# 360_led_stick_5_layer.net
KiCad netlist of a schematic drawn in EAGLE
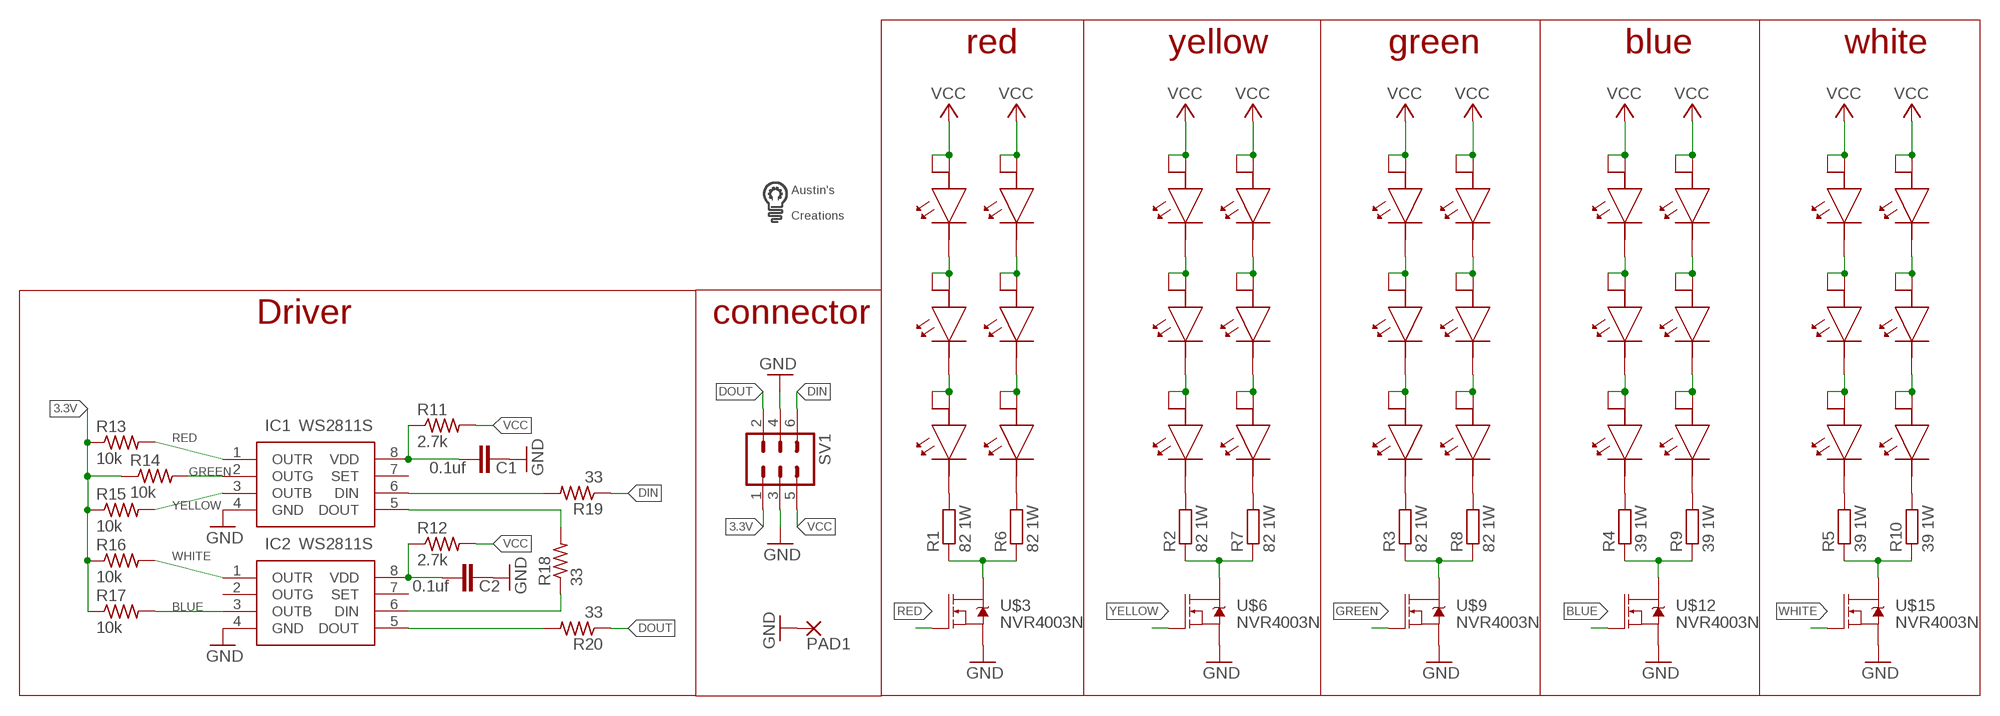
[diagram p0: schematic, sheet 1]

(export (version "E")
  (design (tool "Eeschema 10.0.6"))
  (components
    (comp (ref "C1")
      (value "0.1uf")
      (footprint "eagle-import:C0603K")
      (libsource (lib "eagle-import") (part "C-EUC0603K"))
    )
    (comp (ref "C2")
      (value "0.1uf")
      (footprint "eagle-import:C0603K")
      (libsource (lib "eagle-import") (part "C-EUC0603K"))
    )
    (comp (ref "IC1")
      (value "WS2811S")
      (footprint "eagle-import:SOIC127P600X175-8N")
      (fields (field (name "MANUFACTURER_PART_NUMBER") "ws2811s"))
      (libsource (lib "eagle-import") (part "WS2811S"))
    )
    (comp (ref "IC2")
      (value "WS2811S")
      (footprint "eagle-import:SOIC127P600X175-8N")
      (fields (field (name "MANUFACTURER_PART_NUMBER") "ws2811s"))
      (libsource (lib "eagle-import") (part "WS2811S"))
    )
    (comp (ref "PAD1")
      (value "WIREPADSMD1,27-254")
      (footprint "eagle-import:SMD1,27-2,54")
      (libsource (lib "eagle-import") (part "WIREPADSMD1,27-254"))
    )
    (comp (ref "R1")
      (value "82 1W")
      (footprint "eagle-import:R1210")
      (libsource (lib "eagle-import") (part "R-EU_R1210"))
    )
    (comp (ref "R2")
      (value "82 1W")
      (footprint "eagle-import:R1210")
      (libsource (lib "eagle-import") (part "R-EU_R1210"))
    )
    (comp (ref "R3")
      (value "82 1W")
      (footprint "eagle-import:R1210")
      (libsource (lib "eagle-import") (part "R-EU_R1210"))
    )
    (comp (ref "R4")
      (value "39 1W")
      (footprint "eagle-import:R1210")
      (libsource (lib "eagle-import") (part "R-EU_R1210"))
    )
    (comp (ref "R5")
      (value "39 1W")
      (footprint "eagle-import:R1210")
      (libsource (lib "eagle-import") (part "R-EU_R1210"))
    )
    (comp (ref "R6")
      (value "82 1W")
      (footprint "eagle-import:R1210")
      (libsource (lib "eagle-import") (part "R-EU_R1210"))
    )
    (comp (ref "R7")
      (value "82 1W")
      (footprint "eagle-import:R1210")
      (libsource (lib "eagle-import") (part "R-EU_R1210"))
    )
    (comp (ref "R8")
      (value "82 1W")
      (footprint "eagle-import:R1210")
      (libsource (lib "eagle-import") (part "R-EU_R1210"))
    )
    (comp (ref "R9")
      (value "39 1W")
      (footprint "eagle-import:R1210")
      (libsource (lib "eagle-import") (part "R-EU_R1210"))
    )
    (comp (ref "R10")
      (value "39 1W")
      (footprint "eagle-import:R1210")
      (libsource (lib "eagle-import") (part "R-EU_R1210"))
    )
    (comp (ref "R11")
      (value "2.7k")
      (footprint "eagle-import:R0603")
      (libsource (lib "eagle-import") (part "R-US_R0603"))
    )
    (comp (ref "R12")
      (value "2.7k")
      (footprint "eagle-import:R0603")
      (libsource (lib "eagle-import") (part "R-US_R0603"))
    )
    (comp (ref "R13")
      (value "10k")
      (footprint "eagle-import:R0603")
      (libsource (lib "eagle-import") (part "R-US_R0603"))
    )
    (comp (ref "R14")
      (value "10k")
      (footprint "eagle-import:R0603")
      (libsource (lib "eagle-import") (part "R-US_R0603"))
    )
    (comp (ref "R15")
      (value "10k")
      (footprint "eagle-import:R0603")
      (libsource (lib "eagle-import") (part "R-US_R0603"))
    )
    (comp (ref "R16")
      (value "10k")
      (footprint "eagle-import:R0603")
      (libsource (lib "eagle-import") (part "R-US_R0603"))
    )
    (comp (ref "R17")
      (value "10k")
      (footprint "eagle-import:R0603")
      (libsource (lib "eagle-import") (part "R-US_R0603"))
    )
    (comp (ref "R18")
      (value "33")
      (footprint "eagle-import:R0603")
      (libsource (lib "eagle-import") (part "R-US_R0603"))
    )
    (comp (ref "R19")
      (value "33")
      (footprint "eagle-import:R0603")
      (libsource (lib "eagle-import") (part "R-US_R0603"))
    )
    (comp (ref "R20")
      (value "33")
      (footprint "eagle-import:R0603")
      (libsource (lib "eagle-import") (part "R-US_R0603"))
    )
    (comp (ref "SV1")
      (value "MA03-2")
      (footprint "eagle-import:MA03-2")
      (libsource (lib "eagle-import") (part "MA03-2"))
    )
    (comp (ref "U$1")
      (value "5730LED")
      (footprint "eagle-import:5730LED")
      (libsource (lib "eagle-import") (part "5730LED"))
    )
    (comp (ref "U$2")
      (value "5730LED")
      (footprint "eagle-import:5730LED")
      (libsource (lib "eagle-import") (part "5730LED"))
    )
    (comp (ref "U$3")
      (value "NVR4003N")
      (footprint "eagle-import:SOT23")
      (libsource (lib "eagle-import") (part "NVR4003N"))
    )
    (comp (ref "U$4")
      (value "5730LED")
      (footprint "eagle-import:5730LED")
      (libsource (lib "eagle-import") (part "5730LED"))
    )
    (comp (ref "U$5")
      (value "5730LED")
      (footprint "eagle-import:5730LED")
      (libsource (lib "eagle-import") (part "5730LED"))
    )
    (comp (ref "U$6")
      (value "NVR4003N")
      (footprint "eagle-import:SOT23")
      (libsource (lib "eagle-import") (part "NVR4003N"))
    )
    (comp (ref "U$7")
      (value "5730LED")
      (footprint "eagle-import:5730LED")
      (libsource (lib "eagle-import") (part "5730LED"))
    )
    (comp (ref "U$8")
      (value "5730LED")
      (footprint "eagle-import:5730LED")
      (libsource (lib "eagle-import") (part "5730LED"))
    )
    (comp (ref "U$9")
      (value "NVR4003N")
      (footprint "eagle-import:SOT23")
      (libsource (lib "eagle-import") (part "NVR4003N"))
    )
    (comp (ref "U$10")
      (value "5730LED")
      (footprint "eagle-import:5730LED")
      (libsource (lib "eagle-import") (part "5730LED"))
    )
    (comp (ref "U$11")
      (value "5730LED")
      (footprint "eagle-import:5730LED")
      (libsource (lib "eagle-import") (part "5730LED"))
    )
    (comp (ref "U$12")
      (value "NVR4003N")
      (footprint "eagle-import:SOT23")
      (libsource (lib "eagle-import") (part "NVR4003N"))
    )
    (comp (ref "U$13")
      (value "5730LED")
      (footprint "eagle-import:5730LED")
      (libsource (lib "eagle-import") (part "5730LED"))
    )
    (comp (ref "U$14")
      (value "5730LED")
      (footprint "eagle-import:5730LED")
      (libsource (lib "eagle-import") (part "5730LED"))
    )
    (comp (ref "U$15")
      (value "NVR4003N")
      (footprint "eagle-import:SOT23")
      (libsource (lib "eagle-import") (part "NVR4003N"))
    )
    (comp (ref "U$16")
      (value "5730LED")
      (footprint "eagle-import:5730LED")
      (libsource (lib "eagle-import") (part "5730LED"))
    )
    (comp (ref "U$17")
      (value "5730LED")
      (footprint "eagle-import:5730LED")
      (libsource (lib "eagle-import") (part "5730LED"))
    )
    (comp (ref "U$18")
      (value "5730LED")
      (footprint "eagle-import:5730LED")
      (libsource (lib "eagle-import") (part "5730LED"))
    )
    (comp (ref "U$19")
      (value "5730LED")
      (footprint "eagle-import:5730LED")
      (libsource (lib "eagle-import") (part "5730LED"))
    )
    (comp (ref "U$20")
      (value "5730LED")
      (footprint "eagle-import:5730LED")
      (libsource (lib "eagle-import") (part "5730LED"))
    )
    (comp (ref "U$21")
      (value "LOGO")
      (footprint "eagle-import:LOGO")
      (libsource (lib "eagle-import") (part "LOGO"))
    )
    (comp (ref "U$22")
      (value "5730LED")
      (footprint "eagle-import:5730LED")
      (libsource (lib "eagle-import") (part "5730LED"))
    )
    (comp (ref "U$23")
      (value "5730LED")
      (footprint "eagle-import:5730LED")
      (libsource (lib "eagle-import") (part "5730LED"))
    )
    (comp (ref "U$24")
      (value "5730LED")
      (footprint "eagle-import:5730LED")
      (libsource (lib "eagle-import") (part "5730LED"))
    )
    (comp (ref "U$25")
      (value "5730LED")
      (footprint "eagle-import:5730LED")
      (libsource (lib "eagle-import") (part "5730LED"))
    )
    (comp (ref "U$26")
      (value "5730LED")
      (footprint "eagle-import:5730LED")
      (libsource (lib "eagle-import") (part "5730LED"))
    )
    (comp (ref "U$27")
      (value "5730LED")
      (footprint "eagle-import:5730LED")
      (libsource (lib "eagle-import") (part "5730LED"))
    )
    (comp (ref "U$28")
      (value "5730LED")
      (footprint "eagle-import:5730LED")
      (libsource (lib "eagle-import") (part "5730LED"))
    )
    (comp (ref "U$29")
      (value "5730LED")
      (footprint "eagle-import:5730LED")
      (libsource (lib "eagle-import") (part "5730LED"))
    )
    (comp (ref "U$30")
      (value "5730LED")
      (footprint "eagle-import:5730LED")
      (libsource (lib "eagle-import") (part "5730LED"))
    )
    (comp (ref "U$31")
      (value "5730LED")
      (footprint "eagle-import:5730LED")
      (libsource (lib "eagle-import") (part "5730LED"))
    )
    (comp (ref "U$32")
      (value "5730LED")
      (footprint "eagle-import:5730LED")
      (libsource (lib "eagle-import") (part "5730LED"))
    )
    (comp (ref "U$33")
      (value "5730LED")
      (footprint "eagle-import:5730LED")
      (libsource (lib "eagle-import") (part "5730LED"))
    )
    (comp (ref "U$34")
      (value "5730LED")
      (footprint "eagle-import:5730LED")
      (libsource (lib "eagle-import") (part "5730LED"))
    )
    (comp (ref "U$35")
      (value "5730LED")
      (footprint "eagle-import:5730LED")
      (libsource (lib "eagle-import") (part "5730LED"))
    )
    (comp (ref "U$36")
      (value "5730LED")
      (footprint "eagle-import:5730LED")
      (libsource (lib "eagle-import") (part "5730LED"))
    )
  )
  (nets
    (net (code "1") (name "3.3V") (class "Default")
      (node (ref "R13") (pin "1") (pinfunction "1_1") (pintype "passive"))
      (node (ref "R14") (pin "1") (pinfunction "1_1") (pintype "passive"))
      (node (ref "R15") (pin "1") (pinfunction "1_1") (pintype "passive"))
      (node (ref "R16") (pin "1") (pinfunction "1_1") (pintype "passive"))
      (node (ref "R17") (pin "1") (pinfunction "1_1") (pintype "passive"))
      (node (ref "SV1") (pin "1") (pinfunction "1_1") (pintype "passive"))
    )
    (net (code "2") (name "BLUE") (class "Default")
      (node (ref "IC2") (pin "3") (pinfunction "OUTB_3") (pintype "output"))
      (node (ref "R17") (pin "2") (pinfunction "2_2") (pintype "passive"))
      (node (ref "U$12") (pin "2") (pinfunction "G_2") (pintype "bidirectional"))
    )
    (net (code "3") (name "DIN") (class "Default")
      (node (ref "R19") (pin "1") (pinfunction "1_1") (pintype "passive"))
      (node (ref "SV1") (pin "6") (pinfunction "6_6") (pintype "passive"))
    )
    (net (code "4") (name "DOUT") (class "Default")
      (node (ref "R20") (pin "1") (pinfunction "1_1") (pintype "passive"))
      (node (ref "SV1") (pin "2") (pinfunction "2_2") (pintype "passive"))
    )
    (net (code "5") (name "GND") (class "Default")
      (node (ref "C1") (pin "1") (pinfunction "1_1") (pintype "passive"))
      (node (ref "C2") (pin "1") (pinfunction "1_1") (pintype "passive"))
      (node (ref "IC1") (pin "4") (pinfunction "GND_4") (pintype "power_in"))
      (node (ref "IC2") (pin "4") (pinfunction "GND_4") (pintype "power_in"))
      (node (ref "PAD1") (pin "1") (pinfunction "P_1") (pintype "passive"))
      (node (ref "SV1") (pin "3") (pinfunction "3_3") (pintype "passive"))
      (node (ref "SV1") (pin "4") (pinfunction "4_4") (pintype "passive"))
      (node (ref "U$12") (pin "3") (pinfunction "S_3") (pintype "bidirectional"))
      (node (ref "U$15") (pin "3") (pinfunction "S_3") (pintype "bidirectional"))
      (node (ref "U$3") (pin "3") (pinfunction "S_3") (pintype "bidirectional"))
      (node (ref "U$6") (pin "3") (pinfunction "S_3") (pintype "bidirectional"))
      (node (ref "U$9") (pin "3") (pinfunction "S_3") (pintype "bidirectional"))
    )
    (net (code "6") (name "GREEN") (class "Default")
      (node (ref "IC1") (pin "2") (pinfunction "OUTG_2") (pintype "output"))
      (node (ref "R14") (pin "2") (pinfunction "2_2") (pintype "passive"))
      (node (ref "U$9") (pin "2") (pinfunction "G_2") (pintype "bidirectional"))
    )
    (net (code "7") (name "Net-(IC1-DIN)") (class "Default")
      (node (ref "IC1") (pin "6") (pinfunction "DIN_6") (pintype "input"))
      (node (ref "R19") (pin "2") (pinfunction "2_2") (pintype "passive"))
    )
    (net (code "8") (name "Net-(IC1-DOUT)") (class "Default")
      (node (ref "IC1") (pin "5") (pinfunction "DOUT_5") (pintype "bidirectional"))
      (node (ref "R18") (pin "2") (pinfunction "2_2") (pintype "passive"))
    )
    (net (code "9") (name "Net-(IC1-VDD)") (class "Default")
      (node (ref "C1") (pin "2") (pinfunction "2_2") (pintype "passive"))
      (node (ref "IC1") (pin "8") (pinfunction "VDD_8") (pintype "power_in"))
      (node (ref "R11") (pin "1") (pinfunction "1_1") (pintype "passive"))
    )
    (net (code "10") (name "Net-(IC2-DIN)") (class "Default")
      (node (ref "IC2") (pin "6") (pinfunction "DIN_6") (pintype "input"))
      (node (ref "R18") (pin "1") (pinfunction "1_1") (pintype "passive"))
    )
    (net (code "11") (name "Net-(IC2-DOUT)") (class "Default")
      (node (ref "IC2") (pin "5") (pinfunction "DOUT_5") (pintype "bidirectional"))
      (node (ref "R20") (pin "2") (pinfunction "2_2") (pintype "passive"))
    )
    (net (code "12") (name "Net-(IC2-VDD)") (class "Default")
      (node (ref "C2") (pin "2") (pinfunction "2_2") (pintype "passive"))
      (node (ref "IC2") (pin "8") (pinfunction "VDD_8") (pintype "power_in"))
      (node (ref "R12") (pin "1") (pinfunction "1_1") (pintype "passive"))
    )
    (net (code "13") (name "Net-(R1-Pad2)") (class "Default")
      (node (ref "R1") (pin "2") (pinfunction "2_2") (pintype "passive"))
      (node (ref "U$4") (pin "P$2") (pinfunction "P$2_P$2") (pintype "bidirectional"))
    )
    (net (code "14") (name "Net-(R2-Pad2)") (class "Default")
      (node (ref "R2") (pin "2") (pinfunction "2_2") (pintype "passive"))
      (node (ref "U$8") (pin "P$2") (pinfunction "P$2_P$2") (pintype "bidirectional"))
    )
    (net (code "15") (name "Net-(R3-Pad2)") (class "Default")
      (node (ref "R3") (pin "2") (pinfunction "2_2") (pintype "passive"))
      (node (ref "U$13") (pin "P$2") (pinfunction "P$2_P$2") (pintype "bidirectional"))
    )
    (net (code "16") (name "Net-(R4-Pad2)") (class "Default")
      (node (ref "R4") (pin "2") (pinfunction "2_2") (pintype "passive"))
      (node (ref "U$17") (pin "P$2") (pinfunction "P$2_P$2") (pintype "bidirectional"))
    )
    (net (code "17") (name "Net-(R5-Pad2)") (class "Default")
      (node (ref "R5") (pin "2") (pinfunction "2_2") (pintype "passive"))
      (node (ref "U$20") (pin "P$2") (pinfunction "P$2_P$2") (pintype "bidirectional"))
    )
    (net (code "18") (name "Net-(R6-Pad2)") (class "Default")
      (node (ref "R6") (pin "2") (pinfunction "2_2") (pintype "passive"))
      (node (ref "U$24") (pin "P$2") (pinfunction "P$2_P$2") (pintype "bidirectional"))
    )
    (net (code "19") (name "Net-(R7-Pad2)") (class "Default")
      (node (ref "R7") (pin "2") (pinfunction "2_2") (pintype "passive"))
      (node (ref "U$27") (pin "P$2") (pinfunction "P$2_P$2") (pintype "bidirectional"))
    )
    (net (code "20") (name "Net-(R8-Pad2)") (class "Default")
      (node (ref "R8") (pin "2") (pinfunction "2_2") (pintype "passive"))
      (node (ref "U$30") (pin "P$2") (pinfunction "P$2_P$2") (pintype "bidirectional"))
    )
    (net (code "21") (name "Net-(R9-Pad2)") (class "Default")
      (node (ref "R9") (pin "2") (pinfunction "2_2") (pintype "passive"))
      (node (ref "U$33") (pin "P$2") (pinfunction "P$2_P$2") (pintype "bidirectional"))
    )
    (net (code "22") (name "Net-(R10-Pad2)") (class "Default")
      (node (ref "R10") (pin "2") (pinfunction "2_2") (pintype "passive"))
      (node (ref "U$36") (pin "P$2") (pinfunction "P$2_P$2") (pintype "bidirectional"))
    )
    (net (code "23") (name "Net-(U$1-PadP$2)") (class "Default")
      (node (ref "U$1") (pin "P$2") (pinfunction "P$2_P$2") (pintype "bidirectional"))
      (node (ref "U$2") (pin "P$1") (pinfunction "P$1_P$1") (pintype "bidirectional"))
      (node (ref "U$2") (pin "P$3") (pinfunction "P$3_P$3") (pintype "bidirectional"))
    )
    (net (code "24") (name "Net-(U$2-PadP$2)") (class "Default")
      (node (ref "U$2") (pin "P$2") (pinfunction "P$2_P$2") (pintype "bidirectional"))
      (node (ref "U$4") (pin "P$1") (pinfunction "P$1_P$1") (pintype "bidirectional"))
      (node (ref "U$4") (pin "P$3") (pinfunction "P$3_P$3") (pintype "bidirectional"))
    )
    (net (code "25") (name "Net-(U$3-D)") (class "Default")
      (node (ref "R1") (pin "1") (pinfunction "1_1") (pintype "passive"))
      (node (ref "R6") (pin "1") (pinfunction "1_1") (pintype "passive"))
      (node (ref "U$3") (pin "1") (pinfunction "D_1") (pintype "bidirectional"))
    )
    (net (code "26") (name "Net-(U$5-PadP$2)") (class "Default")
      (node (ref "U$5") (pin "P$2") (pinfunction "P$2_P$2") (pintype "bidirectional"))
      (node (ref "U$7") (pin "P$1") (pinfunction "P$1_P$1") (pintype "bidirectional"))
      (node (ref "U$7") (pin "P$3") (pinfunction "P$3_P$3") (pintype "bidirectional"))
    )
    (net (code "27") (name "Net-(U$6-D)") (class "Default")
      (node (ref "R2") (pin "1") (pinfunction "1_1") (pintype "passive"))
      (node (ref "R7") (pin "1") (pinfunction "1_1") (pintype "passive"))
      (node (ref "U$6") (pin "1") (pinfunction "D_1") (pintype "bidirectional"))
    )
    (net (code "28") (name "Net-(U$7-PadP$2)") (class "Default")
      (node (ref "U$7") (pin "P$2") (pinfunction "P$2_P$2") (pintype "bidirectional"))
      (node (ref "U$8") (pin "P$1") (pinfunction "P$1_P$1") (pintype "bidirectional"))
      (node (ref "U$8") (pin "P$3") (pinfunction "P$3_P$3") (pintype "bidirectional"))
    )
    (net (code "29") (name "Net-(U$9-D)") (class "Default")
      (node (ref "R3") (pin "1") (pinfunction "1_1") (pintype "passive"))
      (node (ref "R8") (pin "1") (pinfunction "1_1") (pintype "passive"))
      (node (ref "U$9") (pin "1") (pinfunction "D_1") (pintype "bidirectional"))
    )
    (net (code "30") (name "Net-(U$10-PadP$2)") (class "Default")
      (node (ref "U$10") (pin "P$2") (pinfunction "P$2_P$2") (pintype "bidirectional"))
      (node (ref "U$11") (pin "P$1") (pinfunction "P$1_P$1") (pintype "bidirectional"))
      (node (ref "U$11") (pin "P$3") (pinfunction "P$3_P$3") (pintype "bidirectional"))
    )
    (net (code "31") (name "Net-(U$11-PadP$2)") (class "Default")
      (node (ref "U$11") (pin "P$2") (pinfunction "P$2_P$2") (pintype "bidirectional"))
      (node (ref "U$13") (pin "P$1") (pinfunction "P$1_P$1") (pintype "bidirectional"))
      (node (ref "U$13") (pin "P$3") (pinfunction "P$3_P$3") (pintype "bidirectional"))
    )
    (net (code "32") (name "Net-(U$12-D)") (class "Default")
      (node (ref "R4") (pin "1") (pinfunction "1_1") (pintype "passive"))
      (node (ref "R9") (pin "1") (pinfunction "1_1") (pintype "passive"))
      (node (ref "U$12") (pin "1") (pinfunction "D_1") (pintype "bidirectional"))
    )
    (net (code "33") (name "Net-(U$14-PadP$2)") (class "Default")
      (node (ref "U$14") (pin "P$2") (pinfunction "P$2_P$2") (pintype "bidirectional"))
      (node (ref "U$16") (pin "P$1") (pinfunction "P$1_P$1") (pintype "bidirectional"))
      (node (ref "U$16") (pin "P$3") (pinfunction "P$3_P$3") (pintype "bidirectional"))
    )
    (net (code "34") (name "Net-(U$15-D)") (class "Default")
      (node (ref "R10") (pin "1") (pinfunction "1_1") (pintype "passive"))
      (node (ref "R5") (pin "1") (pinfunction "1_1") (pintype "passive"))
      (node (ref "U$15") (pin "1") (pinfunction "D_1") (pintype "bidirectional"))
    )
    (net (code "35") (name "Net-(U$16-PadP$2)") (class "Default")
      (node (ref "U$16") (pin "P$2") (pinfunction "P$2_P$2") (pintype "bidirectional"))
      (node (ref "U$17") (pin "P$1") (pinfunction "P$1_P$1") (pintype "bidirectional"))
      (node (ref "U$17") (pin "P$3") (pinfunction "P$3_P$3") (pintype "bidirectional"))
    )
    (net (code "36") (name "Net-(U$18-PadP$2)") (class "Default")
      (node (ref "U$18") (pin "P$2") (pinfunction "P$2_P$2") (pintype "bidirectional"))
      (node (ref "U$19") (pin "P$1") (pinfunction "P$1_P$1") (pintype "bidirectional"))
      (node (ref "U$19") (pin "P$3") (pinfunction "P$3_P$3") (pintype "bidirectional"))
    )
    (net (code "37") (name "Net-(U$19-PadP$2)") (class "Default")
      (node (ref "U$19") (pin "P$2") (pinfunction "P$2_P$2") (pintype "bidirectional"))
      (node (ref "U$20") (pin "P$1") (pinfunction "P$1_P$1") (pintype "bidirectional"))
      (node (ref "U$20") (pin "P$3") (pinfunction "P$3_P$3") (pintype "bidirectional"))
    )
    (net (code "38") (name "Net-(U$22-PadP$2)") (class "Default")
      (node (ref "U$22") (pin "P$2") (pinfunction "P$2_P$2") (pintype "bidirectional"))
      (node (ref "U$23") (pin "P$1") (pinfunction "P$1_P$1") (pintype "bidirectional"))
      (node (ref "U$23") (pin "P$3") (pinfunction "P$3_P$3") (pintype "bidirectional"))
    )
    (net (code "39") (name "Net-(U$23-PadP$2)") (class "Default")
      (node (ref "U$23") (pin "P$2") (pinfunction "P$2_P$2") (pintype "bidirectional"))
      (node (ref "U$24") (pin "P$1") (pinfunction "P$1_P$1") (pintype "bidirectional"))
      (node (ref "U$24") (pin "P$3") (pinfunction "P$3_P$3") (pintype "bidirectional"))
    )
    (net (code "40") (name "Net-(U$25-PadP$2)") (class "Default")
      (node (ref "U$25") (pin "P$2") (pinfunction "P$2_P$2") (pintype "bidirectional"))
      (node (ref "U$26") (pin "P$1") (pinfunction "P$1_P$1") (pintype "bidirectional"))
      (node (ref "U$26") (pin "P$3") (pinfunction "P$3_P$3") (pintype "bidirectional"))
    )
    (net (code "41") (name "Net-(U$26-PadP$2)") (class "Default")
      (node (ref "U$26") (pin "P$2") (pinfunction "P$2_P$2") (pintype "bidirectional"))
      (node (ref "U$27") (pin "P$1") (pinfunction "P$1_P$1") (pintype "bidirectional"))
      (node (ref "U$27") (pin "P$3") (pinfunction "P$3_P$3") (pintype "bidirectional"))
    )
    (net (code "42") (name "Net-(U$28-PadP$2)") (class "Default")
      (node (ref "U$28") (pin "P$2") (pinfunction "P$2_P$2") (pintype "bidirectional"))
      (node (ref "U$29") (pin "P$1") (pinfunction "P$1_P$1") (pintype "bidirectional"))
      (node (ref "U$29") (pin "P$3") (pinfunction "P$3_P$3") (pintype "bidirectional"))
    )
    (net (code "43") (name "Net-(U$29-PadP$2)") (class "Default")
      (node (ref "U$29") (pin "P$2") (pinfunction "P$2_P$2") (pintype "bidirectional"))
      (node (ref "U$30") (pin "P$1") (pinfunction "P$1_P$1") (pintype "bidirectional"))
      (node (ref "U$30") (pin "P$3") (pinfunction "P$3_P$3") (pintype "bidirectional"))
    )
    (net (code "44") (name "Net-(U$31-PadP$2)") (class "Default")
      (node (ref "U$31") (pin "P$2") (pinfunction "P$2_P$2") (pintype "bidirectional"))
      (node (ref "U$32") (pin "P$1") (pinfunction "P$1_P$1") (pintype "bidirectional"))
      (node (ref "U$32") (pin "P$3") (pinfunction "P$3_P$3") (pintype "bidirectional"))
    )
    (net (code "45") (name "Net-(U$32-PadP$2)") (class "Default")
      (node (ref "U$32") (pin "P$2") (pinfunction "P$2_P$2") (pintype "bidirectional"))
      (node (ref "U$33") (pin "P$1") (pinfunction "P$1_P$1") (pintype "bidirectional"))
      (node (ref "U$33") (pin "P$3") (pinfunction "P$3_P$3") (pintype "bidirectional"))
    )
    (net (code "46") (name "Net-(U$34-PadP$2)") (class "Default")
      (node (ref "U$34") (pin "P$2") (pinfunction "P$2_P$2") (pintype "bidirectional"))
      (node (ref "U$35") (pin "P$1") (pinfunction "P$1_P$1") (pintype "bidirectional"))
      (node (ref "U$35") (pin "P$3") (pinfunction "P$3_P$3") (pintype "bidirectional"))
    )
    (net (code "47") (name "Net-(U$35-PadP$2)") (class "Default")
      (node (ref "U$35") (pin "P$2") (pinfunction "P$2_P$2") (pintype "bidirectional"))
      (node (ref "U$36") (pin "P$1") (pinfunction "P$1_P$1") (pintype "bidirectional"))
      (node (ref "U$36") (pin "P$3") (pinfunction "P$3_P$3") (pintype "bidirectional"))
    )
    (net (code "48") (name "RED") (class "Default")
      (node (ref "IC1") (pin "1") (pinfunction "OUTR_1") (pintype "output"))
      (node (ref "R13") (pin "2") (pinfunction "2_2") (pintype "passive"))
      (node (ref "U$3") (pin "2") (pinfunction "G_2") (pintype "bidirectional"))
    )
    (net (code "49") (name "VCC") (class "Default")
      (node (ref "R11") (pin "2") (pinfunction "2_2") (pintype "passive"))
      (node (ref "R12") (pin "2") (pinfunction "2_2") (pintype "passive"))
      (node (ref "SV1") (pin "5") (pinfunction "5_5") (pintype "passive"))
      (node (ref "U$1") (pin "P$1") (pinfunction "P$1_P$1") (pintype "bidirectional"))
      (node (ref "U$1") (pin "P$3") (pinfunction "P$3_P$3") (pintype "bidirectional"))
      (node (ref "U$10") (pin "P$1") (pinfunction "P$1_P$1") (pintype "bidirectional"))
      (node (ref "U$10") (pin "P$3") (pinfunction "P$3_P$3") (pintype "bidirectional"))
      (node (ref "U$14") (pin "P$1") (pinfunction "P$1_P$1") (pintype "bidirectional"))
      (node (ref "U$14") (pin "P$3") (pinfunction "P$3_P$3") (pintype "bidirectional"))
      (node (ref "U$18") (pin "P$1") (pinfunction "P$1_P$1") (pintype "bidirectional"))
      (node (ref "U$18") (pin "P$3") (pinfunction "P$3_P$3") (pintype "bidirectional"))
      (node (ref "U$22") (pin "P$1") (pinfunction "P$1_P$1") (pintype "bidirectional"))
      (node (ref "U$22") (pin "P$3") (pinfunction "P$3_P$3") (pintype "bidirectional"))
      (node (ref "U$25") (pin "P$1") (pinfunction "P$1_P$1") (pintype "bidirectional"))
      (node (ref "U$25") (pin "P$3") (pinfunction "P$3_P$3") (pintype "bidirectional"))
      (node (ref "U$28") (pin "P$1") (pinfunction "P$1_P$1") (pintype "bidirectional"))
      (node (ref "U$28") (pin "P$3") (pinfunction "P$3_P$3") (pintype "bidirectional"))
      (node (ref "U$31") (pin "P$1") (pinfunction "P$1_P$1") (pintype "bidirectional"))
      (node (ref "U$31") (pin "P$3") (pinfunction "P$3_P$3") (pintype "bidirectional"))
      (node (ref "U$34") (pin "P$1") (pinfunction "P$1_P$1") (pintype "bidirectional"))
      (node (ref "U$34") (pin "P$3") (pinfunction "P$3_P$3") (pintype "bidirectional"))
      (node (ref "U$5") (pin "P$1") (pinfunction "P$1_P$1") (pintype "bidirectional"))
      (node (ref "U$5") (pin "P$3") (pinfunction "P$3_P$3") (pintype "bidirectional"))
    )
    (net (code "50") (name "WHITE") (class "Default")
      (node (ref "IC2") (pin "1") (pinfunction "OUTR_1") (pintype "output"))
      (node (ref "R16") (pin "2") (pinfunction "2_2") (pintype "passive"))
      (node (ref "U$15") (pin "2") (pinfunction "G_2") (pintype "bidirectional"))
    )
    (net (code "51") (name "YELLOW") (class "Default")
      (node (ref "IC1") (pin "3") (pinfunction "OUTB_3") (pintype "output"))
      (node (ref "R15") (pin "2") (pinfunction "2_2") (pintype "passive"))
      (node (ref "U$6") (pin "2") (pinfunction "G_2") (pintype "bidirectional"))
    )
    (net (code "52") (name "unconnected-(IC1-SET-Pad7)") (class "Default")
      (node (ref "IC1") (pin "7") (pinfunction "SET_7") (pintype "input"))
    )
    (net (code "53") (name "unconnected-(IC2-OUTG-Pad2)") (class "Default")
      (node (ref "IC2") (pin "2") (pinfunction "OUTG_2") (pintype "output"))
    )
    (net (code "54") (name "unconnected-(IC2-SET-Pad7)") (class "Default")
      (node (ref "IC2") (pin "7") (pinfunction "SET_7") (pintype "input"))
    )
  )
)
